# TopLevel.net
KiCad netlist of a schematic drawn in Altium Designer
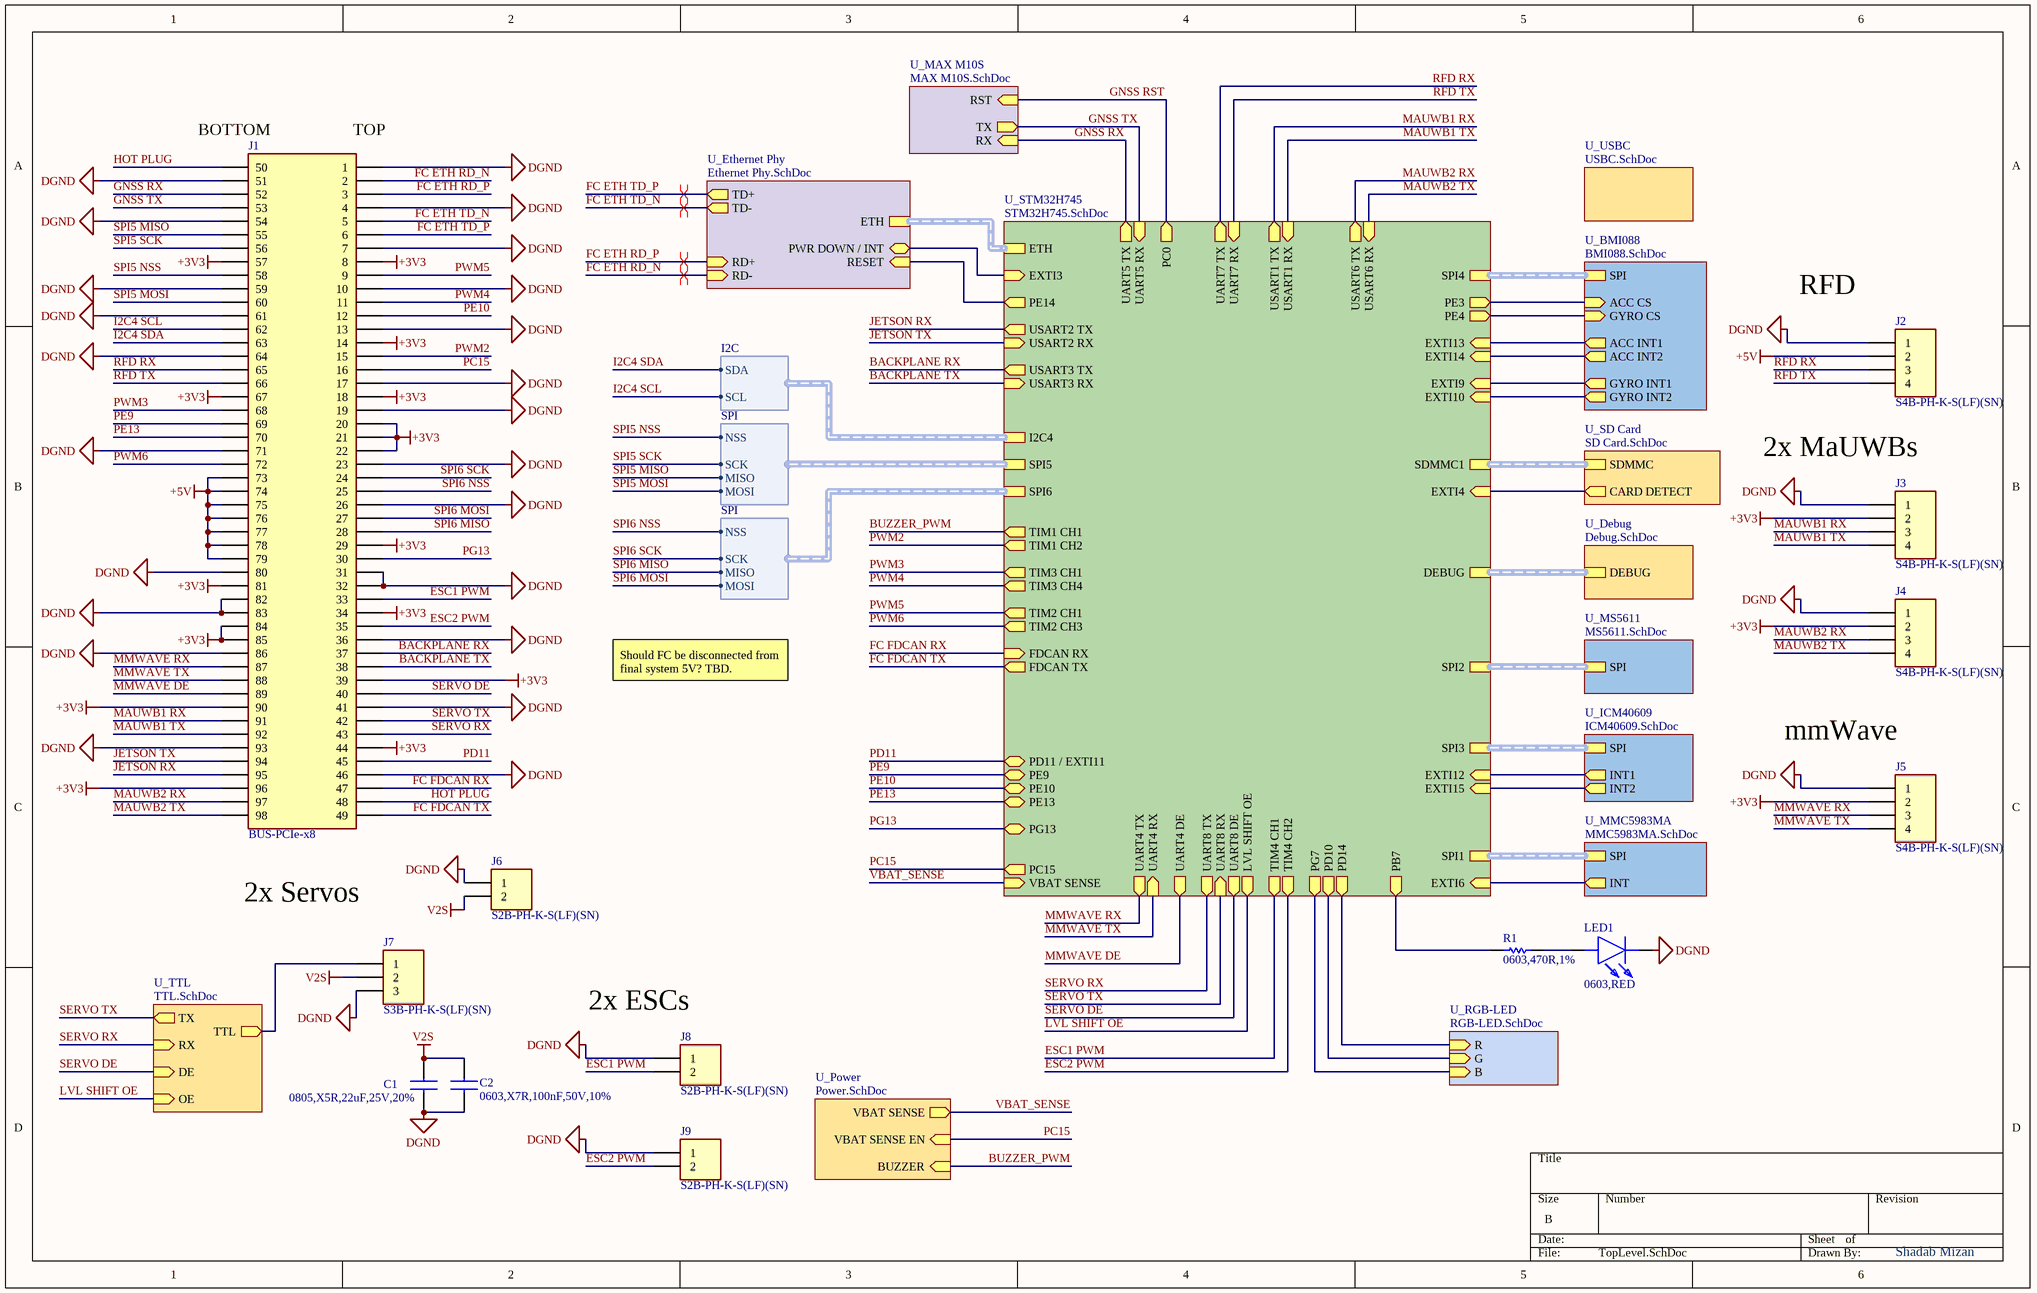
[diagram p0: TopLevel.SchDoc]

(export (version "E")
  (design (tool "Eeschema 10.0.6"))
  (components
    (comp (ref "C1")
      (value "0805,X5R,22uF,25V,20%")
      (footprint "CAPC2012X145N")
      (description "22uF ±20% 25V Ceramic Capacitor X5R 0805")
      (fields (field (name "LCSC PART #") "C45783") (field (name "MANU PART #") "CL21A226MAQNNNE"))
      (libsource (lib "flight-controller") (part "CL21A226MAQNNNE"))
    )
    (comp (ref "C2")
      (value "0603,X7R,100nF,50V,10%")
      (footprint "CAPC1608X90N")
      (description "50V 100nF X7R ±10% 0603 Multilayer Ceramic Capacitors MLCC - SMD/SMT ROHS")
      (fields (field (name "LCSC PART #") "C14663") (field (name "MANU PART #") "CC0603KRX7R9BB104"))
      (libsource (lib "flight-controller") (part "CC0603KRX7R9BB104"))
    )
    (comp (ref "J1")
      (value "BUS-PCIe-x8")
      (footprint "BUS_PCIexpress_x8")
      (description "PCIe x8")
      (libsource (lib "flight-controller") (part "BUS-PCIe-x8"))
    )
    (comp (ref "J2")
      (value "S4B-PH-K-S(LF)(SN)")
      (footprint "S4B-PH-K-S-_LF_SN")
      (description "Connector Header 4 position 2mm Pitch 2A Right Angle -25℃~+85℃")
      (fields (field (name "LCSC PART #") "C157926"))
      (libsource (lib "flight-controller") (part "S4B-PH-K-S(LF)(SN)"))
    )
    (comp (ref "J3")
      (value "S4B-PH-K-S(LF)(SN)")
      (footprint "S4B-PH-K-S-_LF_SN")
      (description "Connector Header 4 position 2mm Pitch 2A Right Angle -25℃~+85℃")
      (fields (field (name "LCSC PART #") "C157926"))
      (libsource (lib "flight-controller") (part "S4B-PH-K-S(LF)(SN)"))
    )
    (comp (ref "J4")
      (value "S4B-PH-K-S(LF)(SN)")
      (footprint "S4B-PH-K-S-_LF_SN")
      (description "Connector Header 4 position 2mm Pitch 2A Right Angle -25℃~+85℃")
      (fields (field (name "LCSC PART #") "C157926"))
      (libsource (lib "flight-controller") (part "S4B-PH-K-S(LF)(SN)"))
    )
    (comp (ref "J5")
      (value "S4B-PH-K-S(LF)(SN)")
      (footprint "S4B-PH-K-S-_LF_SN")
      (description "Connector Header 4 position 2mm Pitch 2A Right Angle -25℃~+85℃")
      (fields (field (name "LCSC PART #") "C157926"))
      (libsource (lib "flight-controller") (part "S4B-PH-K-S(LF)(SN)"))
    )
    (comp (ref "J6")
      (value "S2B-PH-K-S(LF)(SN)")
      (footprint "S2B-PH-K-S_LF_SN")
      (description "Connector Header 2 position 2mm Pitch 2A Right Angle -25℃~+85℃")
      (fields (field (name "LCSC PART #") "C173752"))
      (libsource (lib "flight-controller") (part "S2B-PH-K-S(LF)(SN)"))
    )
    (comp (ref "J7")
      (value "S3B-PH-K-S(LF)(SN)")
      (footprint "S3B-PH-K-S-_LF_SN")
      (description "Connector Header 3 position 2mm Pitch 2A Right Angle -25℃~+85℃")
      (fields (field (name "LCSC PART #") "C157929"))
      (libsource (lib "flight-controller") (part "S3B-PH-K-S(LF)(SN)"))
    )
    (comp (ref "J8")
      (value "S2B-PH-K-S(LF)(SN)")
      (footprint "S2B-PH-K-S_LF_SN")
      (description "Connector Header 2 position 2mm Pitch 2A Right Angle -25℃~+85℃")
      (fields (field (name "LCSC PART #") "C173752"))
      (libsource (lib "flight-controller") (part "S2B-PH-K-S(LF)(SN)"))
    )
    (comp (ref "J9")
      (value "S2B-PH-K-S(LF)(SN)")
      (footprint "S2B-PH-K-S_LF_SN")
      (description "Connector Header 2 position 2mm Pitch 2A Right Angle -25℃~+85℃")
      (fields (field (name "LCSC PART #") "C173752"))
      (libsource (lib "flight-controller") (part "S2B-PH-K-S(LF)(SN)"))
    )
    (comp (ref "LED1")
      (value "0603,RED")
      (footprint "LEDC1608X36N")
      (fields (field (name "MANU PART #") "KT-0603R") (field (name "LCSC PART #") "C2286"))
      (libsource (lib "flight-controller") (part "KT-0603R"))
    )
    (comp (ref "R1")
      (value "0603,470R,1%")
      (footprint "RESC1608X90N")
      (fields (field (name "LCSC PART #") "C23179") (field (name "MANU PART #") "0603WAF4700T5E"))
      (libsource (lib "flight-controller") (part "0603WAF4700T5E"))
    )
  )
  (nets
    (net (code "3") (name "+3V3") (class "Default")
      (node (ref "J1") (pin "14") (pinfunction "14_14") (pintype "passive"))
      (node (ref "J1") (pin "18") (pinfunction "18_18") (pintype "passive"))
      (node (ref "J1") (pin "20") (pinfunction "20_20") (pintype "passive"))
      (node (ref "J1") (pin "21") (pinfunction "21_21") (pintype "passive"))
      (node (ref "J1") (pin "22") (pinfunction "22_22") (pintype "passive"))
      (node (ref "J1") (pin "29") (pinfunction "29_29") (pintype "passive"))
      (node (ref "J1") (pin "34") (pinfunction "34_34") (pintype "passive"))
      (node (ref "J1") (pin "39") (pinfunction "39_39") (pintype "passive"))
      (node (ref "J1") (pin "44") (pinfunction "44_44") (pintype "passive"))
      (node (ref "J1") (pin "57") (pinfunction "57_57") (pintype "passive"))
      (node (ref "J1") (pin "67") (pinfunction "67_67") (pintype "passive"))
      (node (ref "J1") (pin "8") (pinfunction "8_8") (pintype "passive"))
      (node (ref "J1") (pin "81") (pinfunction "81_81") (pintype "passive"))
      (node (ref "J1") (pin "84") (pinfunction "84_84") (pintype "passive"))
      (node (ref "J1") (pin "85") (pinfunction "85_85") (pintype "passive"))
      (node (ref "J1") (pin "90") (pinfunction "90_90") (pintype "passive"))
      (node (ref "J1") (pin "96") (pinfunction "96_96") (pintype "passive"))
      (node (ref "J3") (pin "2") (pinfunction "2_2") (pintype "passive"))
      (node (ref "J4") (pin "2") (pinfunction "2_2") (pintype "passive"))
      (node (ref "J5") (pin "2") (pinfunction "2_2") (pintype "passive"))
    )
    (net (code "4") (name "+5V") (class "Default")
      (node (ref "J1") (pin "73") (pinfunction "73_73") (pintype "passive"))
      (node (ref "J1") (pin "74") (pinfunction "74_74") (pintype "passive"))
      (node (ref "J1") (pin "75") (pinfunction "75_75") (pintype "passive"))
      (node (ref "J1") (pin "76") (pinfunction "76_76") (pintype "passive"))
      (node (ref "J1") (pin "77") (pinfunction "77_77") (pintype "passive"))
      (node (ref "J1") (pin "78") (pinfunction "78_78") (pintype "passive"))
      (node (ref "J1") (pin "79") (pinfunction "79_79") (pintype "passive"))
      (node (ref "J2") (pin "2") (pinfunction "2_2") (pintype "passive"))
    )
    (net (code "8") (name "/BACKPLANE RX") (class "Default")
      (node (ref "J1") (pin "37") (pinfunction "37_37") (pintype "passive"))
    )
    (net (code "9") (name "/BACKPLANE TX") (class "Default")
      (node (ref "J1") (pin "38") (pinfunction "38_38") (pintype "passive"))
    )
    (net (code "13") (name "/ESC1 PWM") (class "Default")
      (node (ref "J1") (pin "33") (pinfunction "33_33") (pintype "passive"))
      (node (ref "J8") (pin "2") (pinfunction "2_2") (pintype "passive"))
    )
    (net (code "14") (name "/ESC2 PWM") (class "Default")
      (node (ref "J1") (pin "35") (pinfunction "35_35") (pintype "passive"))
      (node (ref "J9") (pin "2") (pinfunction "2_2") (pintype "passive"))
    )
    (net (code "17") (name "/FC ETH RD_N") (class "Default")
      (node (ref "J1") (pin "2") (pinfunction "2_2") (pintype "passive"))
    )
    (net (code "18") (name "/FC ETH RD_P") (class "Default")
      (node (ref "J1") (pin "3") (pinfunction "3_3") (pintype "passive"))
    )
    (net (code "19") (name "/FC ETH TD_N") (class "Default")
      (node (ref "J1") (pin "5") (pinfunction "5_5") (pintype "passive"))
    )
    (net (code "20") (name "/FC ETH TD_P") (class "Default")
      (node (ref "J1") (pin "6") (pinfunction "6_6") (pintype "passive"))
    )
    (net (code "21") (name "/FC FDCAN RX") (class "Default")
      (node (ref "J1") (pin "47") (pinfunction "47_47") (pintype "passive"))
    )
    (net (code "22") (name "/FC FDCAN TX") (class "Default")
      (node (ref "J1") (pin "49") (pinfunction "49_49") (pintype "passive"))
    )
    (net (code "24") (name "/GNSS RX") (class "Default")
      (node (ref "J1") (pin "52") (pinfunction "52_52") (pintype "passive"))
    )
    (net (code "25") (name "/GNSS TX") (class "Default")
      (node (ref "J1") (pin "53") (pinfunction "53_53") (pintype "passive"))
    )
    (net (code "28") (name "/HOT PLUG") (class "Default")
      (node (ref "J1") (pin "48") (pinfunction "48_48") (pintype "passive"))
      (node (ref "J1") (pin "50") (pinfunction "50_50") (pintype "passive"))
    )
    (net (code "29") (name "/I2C4 SCL") (class "Default")
      (node (ref "J1") (pin "62") (pinfunction "62_62") (pintype "passive"))
    )
    (net (code "30") (name "/I2C4 SDA") (class "Default")
      (node (ref "J1") (pin "63") (pinfunction "63_63") (pintype "passive"))
    )
    (net (code "34") (name "/JETSON RX") (class "Default")
      (node (ref "J1") (pin "95") (pinfunction "95_95") (pintype "passive"))
    )
    (net (code "35") (name "/JETSON TX") (class "Default")
      (node (ref "J1") (pin "94") (pinfunction "94_94") (pintype "passive"))
    )
    (net (code "37") (name "/MAUWB1 RX") (class "Default")
      (node (ref "J1") (pin "91") (pinfunction "91_91") (pintype "passive"))
      (node (ref "J3") (pin "3") (pinfunction "3_3") (pintype "passive"))
    )
    (net (code "38") (name "/MAUWB1 TX") (class "Default")
      (node (ref "J1") (pin "92") (pinfunction "92_92") (pintype "passive"))
      (node (ref "J3") (pin "4") (pinfunction "4_4") (pintype "passive"))
    )
    (net (code "39") (name "/MAUWB2 RX") (class "Default")
      (node (ref "J1") (pin "97") (pinfunction "97_97") (pintype "passive"))
      (node (ref "J4") (pin "3") (pinfunction "3_3") (pintype "passive"))
    )
    (net (code "40") (name "/MAUWB2 TX") (class "Default")
      (node (ref "J1") (pin "98") (pinfunction "98_98") (pintype "passive"))
      (node (ref "J4") (pin "4") (pinfunction "4_4") (pintype "passive"))
    )
    (net (code "41") (name "/MMWAVE DE") (class "Default")
      (node (ref "J1") (pin "89") (pinfunction "89_89") (pintype "passive"))
    )
    (net (code "42") (name "/MMWAVE RX") (class "Default")
      (node (ref "J1") (pin "87") (pinfunction "87_87") (pintype "passive"))
      (node (ref "J5") (pin "3") (pinfunction "3_3") (pintype "passive"))
    )
    (net (code "43") (name "/MMWAVE TX") (class "Default")
      (node (ref "J1") (pin "88") (pinfunction "88_88") (pintype "passive"))
      (node (ref "J5") (pin "4") (pinfunction "4_4") (pintype "passive"))
    )
    (net (code "44") (name "/PB7") (class "Default")
      (node (ref "R1") (pin "1") (pinfunction "1_1") (pintype "passive"))
    )
    (net (code "45") (name "/PC15") (class "Default")
      (node (ref "J1") (pin "16") (pinfunction "16_16") (pintype "passive"))
    )
    (net (code "47") (name "/PD11") (class "Default")
      (node (ref "J1") (pin "45") (pinfunction "45_45") (pintype "passive"))
    )
    (net (code "51") (name "/PE9") (class "Default")
      (node (ref "J1") (pin "69") (pinfunction "69_69") (pintype "passive"))
    )
    (net (code "52") (name "/PE10") (class "Default")
      (node (ref "J1") (pin "12") (pinfunction "12_12") (pintype "passive"))
    )
    (net (code "53") (name "/PE13") (class "Default")
      (node (ref "J1") (pin "70") (pinfunction "70_70") (pintype "passive"))
    )
    (net (code "56") (name "/PG13") (class "Default")
      (node (ref "J1") (pin "30") (pinfunction "30_30") (pintype "passive"))
    )
    (net (code "57") (name "/PWM2") (class "Default")
      (node (ref "J1") (pin "15") (pinfunction "15_15") (pintype "passive"))
    )
    (net (code "58") (name "/PWM3") (class "Default")
      (node (ref "J1") (pin "68") (pinfunction "68_68") (pintype "passive"))
    )
    (net (code "59") (name "/PWM4") (class "Default")
      (node (ref "J1") (pin "11") (pinfunction "11_11") (pintype "passive"))
    )
    (net (code "60") (name "/PWM5") (class "Default")
      (node (ref "J1") (pin "9") (pinfunction "9_9") (pintype "passive"))
    )
    (net (code "61") (name "/PWM6") (class "Default")
      (node (ref "J1") (pin "72") (pinfunction "72_72") (pintype "passive"))
    )
    (net (code "62") (name "/RFD RX") (class "Default")
      (node (ref "J1") (pin "65") (pinfunction "65_65") (pintype "passive"))
      (node (ref "J2") (pin "3") (pinfunction "3_3") (pintype "passive"))
    )
    (net (code "63") (name "/RFD TX") (class "Default")
      (node (ref "J1") (pin "66") (pinfunction "66_66") (pintype "passive"))
      (node (ref "J2") (pin "4") (pinfunction "4_4") (pintype "passive"))
    )
    (net (code "65") (name "/SERVO DE") (class "Default")
      (node (ref "J1") (pin "40") (pinfunction "40_40") (pintype "passive"))
    )
    (net (code "66") (name "/SERVO RX") (class "Default")
      (node (ref "J1") (pin "43") (pinfunction "43_43") (pintype "passive"))
    )
    (net (code "67") (name "/SERVO TX") (class "Default")
      (node (ref "J1") (pin "42") (pinfunction "42_42") (pintype "passive"))
    )
    (net (code "72") (name "/SPI5 MISO") (class "Default")
      (node (ref "J1") (pin "55") (pinfunction "55_55") (pintype "passive"))
    )
    (net (code "73") (name "/SPI5 MOSI") (class "Default")
      (node (ref "J1") (pin "60") (pinfunction "60_60") (pintype "passive"))
    )
    (net (code "74") (name "/SPI5 NSS") (class "Default")
      (node (ref "J1") (pin "58") (pinfunction "58_58") (pintype "passive"))
    )
    (net (code "75") (name "/SPI5 SCK") (class "Default")
      (node (ref "J1") (pin "56") (pinfunction "56_56") (pintype "passive"))
    )
    (net (code "76") (name "/SPI6 MISO") (class "Default")
      (node (ref "J1") (pin "28") (pinfunction "28_28") (pintype "passive"))
    )
    (net (code "77") (name "/SPI6 MOSI") (class "Default")
      (node (ref "J1") (pin "27") (pinfunction "27_27") (pintype "passive"))
    )
    (net (code "78") (name "/SPI6 NSS") (class "Default")
      (node (ref "J1") (pin "25") (pinfunction "25_25") (pintype "passive"))
    )
    (net (code "79") (name "/SPI6 SCK") (class "Default")
      (node (ref "J1") (pin "24") (pinfunction "24_24") (pintype "passive"))
    )
    (net (code "80") (name "/TTL") (class "Default")
      (node (ref "J7") (pin "1") (pinfunction "1_1") (pintype "passive"))
    )
    (net (code "84") (name "DGND") (class "Default")
      (node (ref "C1") (pin "1") (pinfunction "1_1") (pintype "passive"))
      (node (ref "C2") (pin "1") (pinfunction "1_1") (pintype "passive"))
      (node (ref "J1") (pin "1") (pinfunction "1_1") (pintype "passive"))
      (node (ref "J1") (pin "10") (pinfunction "10_10") (pintype "passive"))
      (node (ref "J1") (pin "13") (pinfunction "13_13") (pintype "passive"))
      (node (ref "J1") (pin "17") (pinfunction "17_17") (pintype "passive"))
      (node (ref "J1") (pin "19") (pinfunction "19_19") (pintype "passive"))
      (node (ref "J1") (pin "23") (pinfunction "23_23") (pintype "passive"))
      (node (ref "J1") (pin "26") (pinfunction "26_26") (pintype "passive"))
      (node (ref "J1") (pin "31") (pinfunction "31_31") (pintype "passive"))
      (node (ref "J1") (pin "32") (pinfunction "32_32") (pintype "passive"))
      (node (ref "J1") (pin "36") (pinfunction "36_36") (pintype "passive"))
      (node (ref "J1") (pin "4") (pinfunction "4_4") (pintype "passive"))
      (node (ref "J1") (pin "41") (pinfunction "41_41") (pintype "passive"))
      (node (ref "J1") (pin "46") (pinfunction "46_46") (pintype "passive"))
      (node (ref "J1") (pin "51") (pinfunction "51_51") (pintype "passive"))
      (node (ref "J1") (pin "54") (pinfunction "54_54") (pintype "passive"))
      (node (ref "J1") (pin "59") (pinfunction "59_59") (pintype "passive"))
      (node (ref "J1") (pin "61") (pinfunction "61_61") (pintype "passive"))
      (node (ref "J1") (pin "64") (pinfunction "64_64") (pintype "passive"))
      (node (ref "J1") (pin "7") (pinfunction "7_7") (pintype "passive"))
      (node (ref "J1") (pin "71") (pinfunction "71_71") (pintype "passive"))
      (node (ref "J1") (pin "80") (pinfunction "80_80") (pintype "passive"))
      (node (ref "J1") (pin "82") (pinfunction "82_82") (pintype "passive"))
      (node (ref "J1") (pin "83") (pinfunction "83_83") (pintype "passive"))
      (node (ref "J1") (pin "86") (pinfunction "86_86") (pintype "passive"))
      (node (ref "J1") (pin "93") (pinfunction "93_93") (pintype "passive"))
      (node (ref "J2") (pin "1") (pinfunction "1_1") (pintype "passive"))
      (node (ref "J3") (pin "1") (pinfunction "1_1") (pintype "passive"))
      (node (ref "J4") (pin "1") (pinfunction "1_1") (pintype "passive"))
      (node (ref "J5") (pin "1") (pinfunction "1_1") (pintype "passive"))
      (node (ref "J6") (pin "1") (pinfunction "1_1") (pintype "passive"))
      (node (ref "J7") (pin "3") (pinfunction "3_3") (pintype "passive"))
      (node (ref "J8") (pin "1") (pinfunction "1_1") (pintype "passive"))
      (node (ref "J9") (pin "1") (pinfunction "1_1") (pintype "passive"))
      (node (ref "LED1") (pin "1") (pinfunction "K_1") (pintype "passive"))
    )
    (net (code "85") (name "Net-(LED1-A)") (class "Default")
      (node (ref "LED1") (pin "2") (pinfunction "A_2") (pintype "passive"))
      (node (ref "R1") (pin "2") (pinfunction "2_2") (pintype "passive"))
    )
    (net (code "86") (name "V2S") (class "Default")
      (node (ref "C1") (pin "2") (pinfunction "2_2") (pintype "passive"))
      (node (ref "C2") (pin "2") (pinfunction "2_2") (pintype "passive"))
      (node (ref "J6") (pin "2") (pinfunction "2_2") (pintype "passive"))
      (node (ref "J7") (pin "2") (pinfunction "2_2") (pintype "passive"))
    )
  )
)
